# Thermal_CCM.net
KiCad netlist of a schematic drawn in Altium Designer
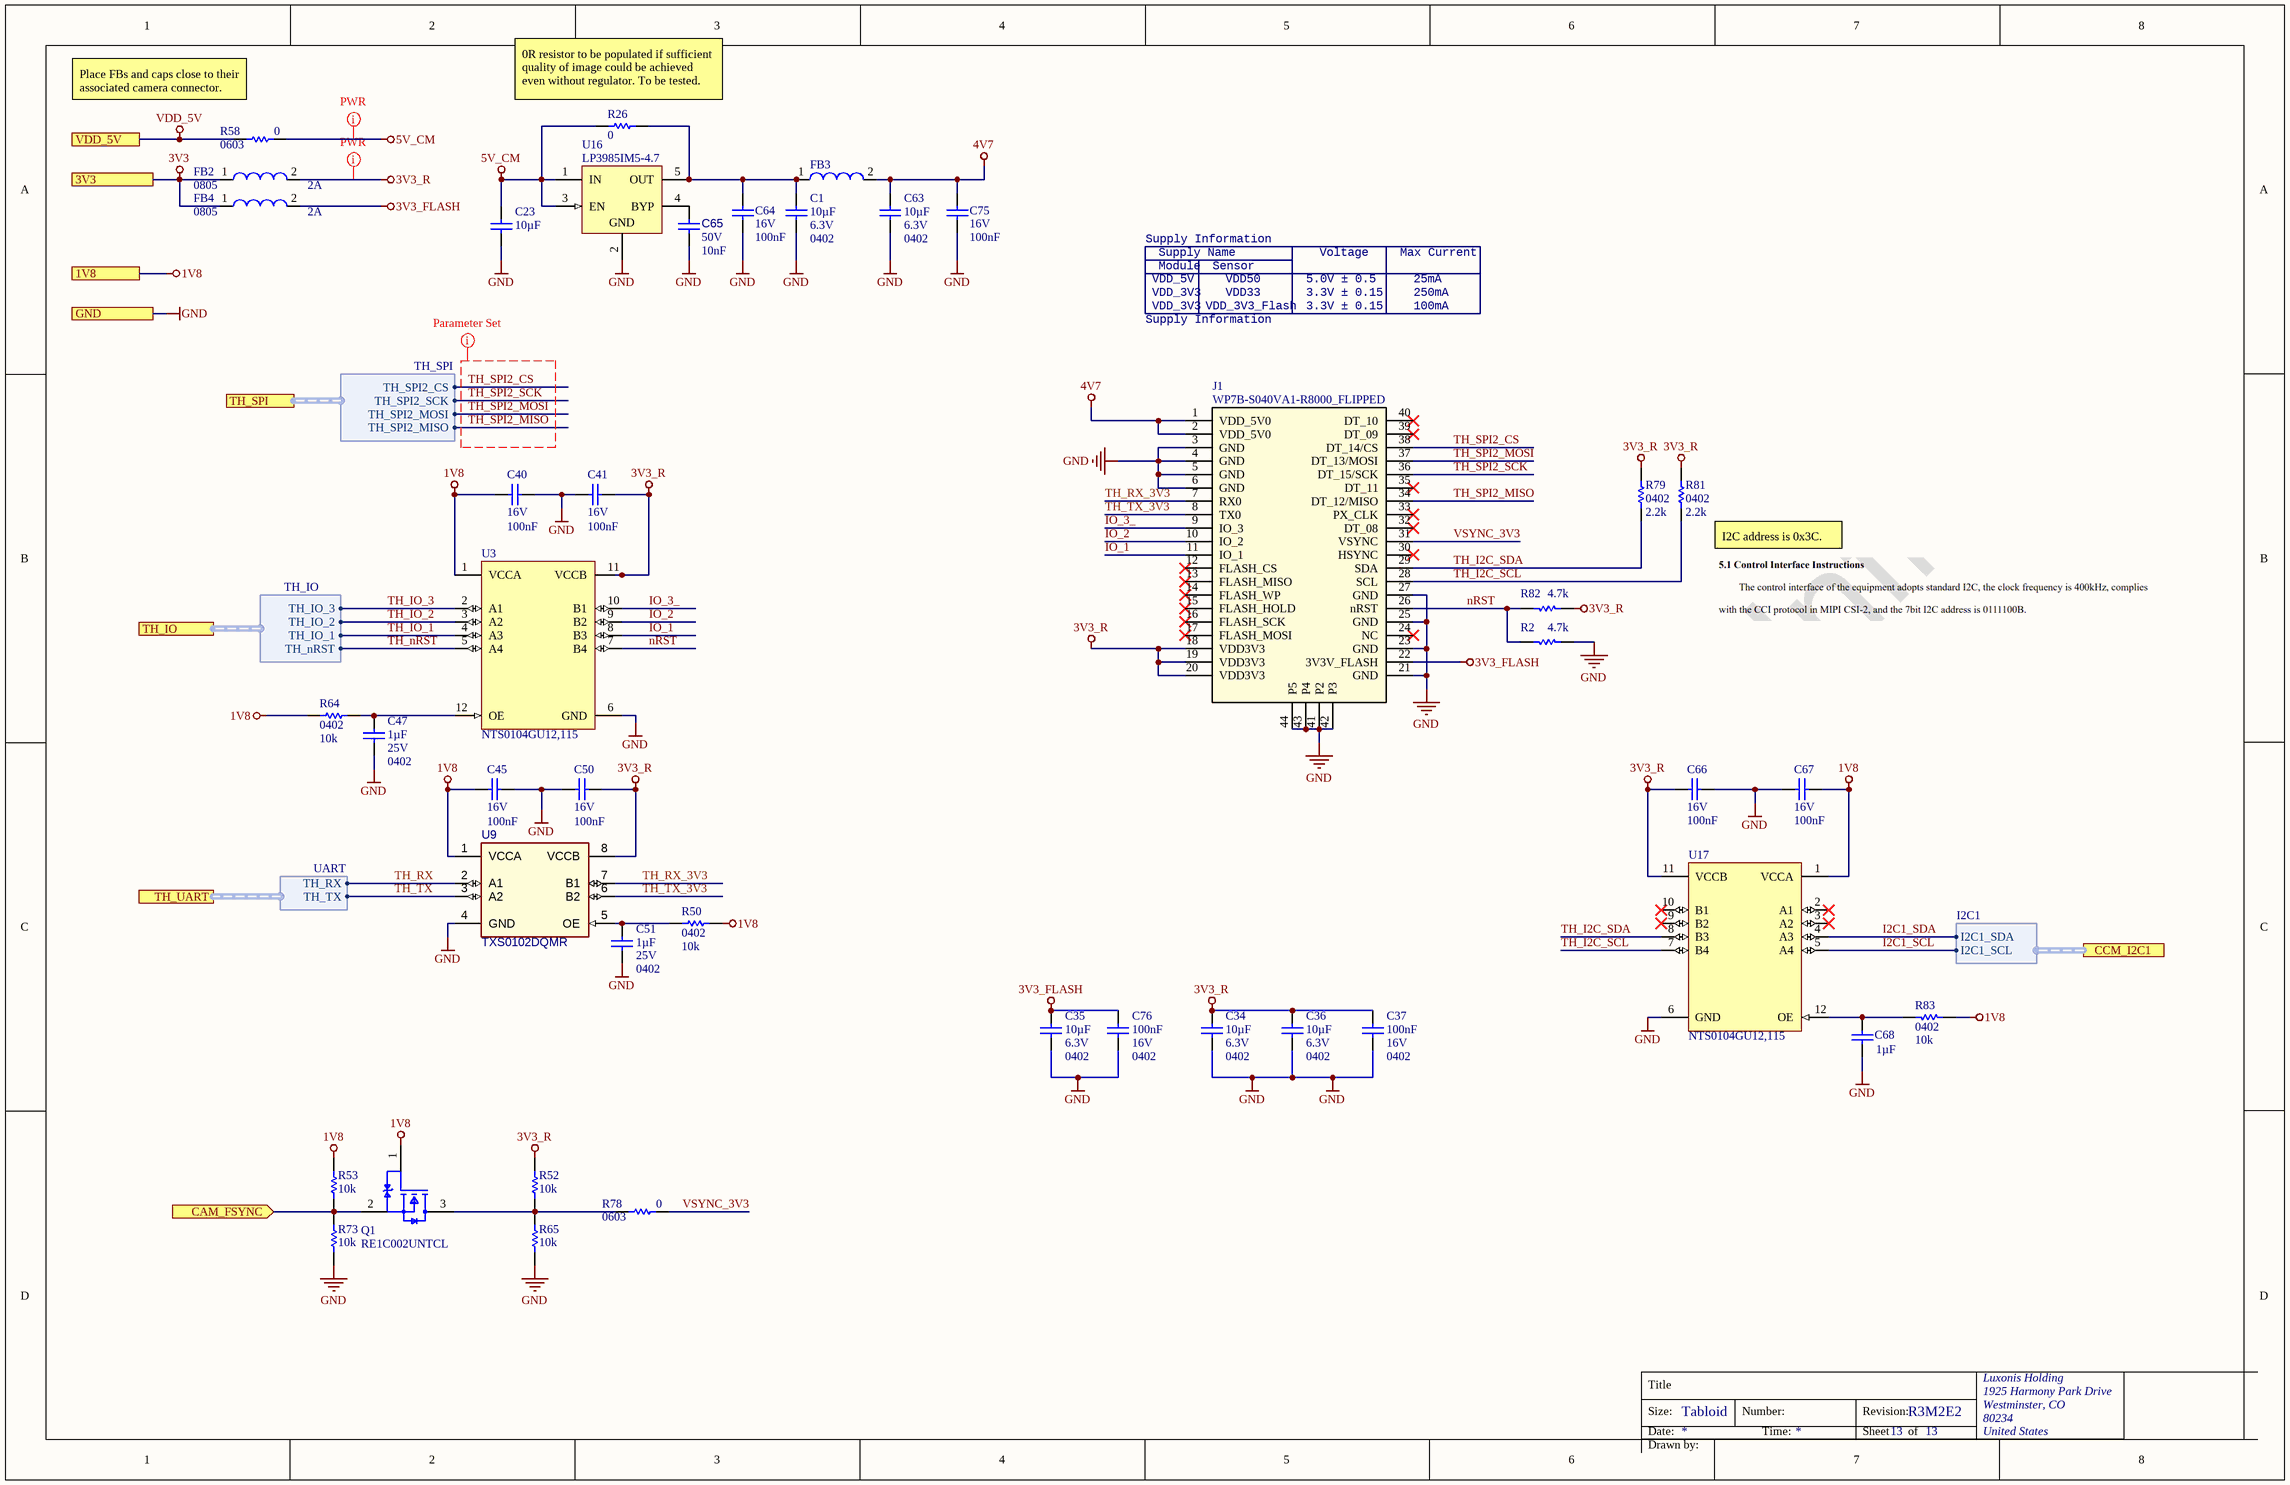
[diagram p0: Thermal_CCM.SchDoc]

(export (version "E")
  (design (tool "Eeschema 10.0.6"))
  (components
    (comp (ref "C1")
      (value "10µF")
      (footprint "CAPC0402(1005)70_N")
      (description "CAP CER 10UF 6.3V X5R 0402 20%")
      (fields
        (field (name "VOLTAGE RATING") "6.3V")
        (field (name "CASE/PACKAGE") "0402")
        (field (name "TOLERANCE") "20%")
        (field (name "Comment") "GRM155R60J106ME15D")
      )
      (libsource (lib "Luxonis LLC") (part "LLL153C70G474ME17E"))
    )
    (comp (ref "C23")
      (value "10µF")
      (footprint "CAPC0402(1005)70_L")
      (description "CAP CER 10UF 6.3V X5R 0402 20%")
      (fields (field (name "TOLERANCE") "20%") (field (name "Comment") "GRM155R60J106ME15D"))
      (libsource (lib "Luxonis LLC") (part "LLL153C70G474ME17E"))
    )
    (comp (ref "C34")
      (value "10µF")
      (footprint "CAPC0402(1005)70_L")
      (description "CAP CER 10UF 6.3V X5R 0402 20%")
      (fields
        (field (name "VOLTAGE RATING") "6.3V")
        (field (name "CASE/PACKAGE") "0402")
        (field (name "TOLERANCE") "20%")
        (field (name "Comment") "GRM155R60J106ME15D")
      )
      (libsource (lib "Luxonis LLC") (part "LLL153C70G474ME17E"))
    )
    (comp (ref "C35")
      (value "10µF")
      (footprint "CAPC0402(1005)70_L")
      (description "CAP CER 10UF 6.3V X5R 0402 20%")
      (fields
        (field (name "VOLTAGE RATING") "6.3V")
        (field (name "CASE/PACKAGE") "0402")
        (field (name "TOLERANCE") "20%")
        (field (name "Comment") "GRM155R60J106ME15D")
      )
      (libsource (lib "Luxonis LLC") (part "LLL153C70G474ME17E"))
    )
    (comp (ref "C36")
      (value "10µF")
      (footprint "CAPC0402(1005)70_L")
      (description "CAP CER 10UF 6.3V X5R 0402 20%")
      (fields
        (field (name "VOLTAGE RATING") "6.3V")
        (field (name "CASE/PACKAGE") "0402")
        (field (name "TOLERANCE") "20%")
        (field (name "Comment") "GRM155R60J106ME15D")
      )
      (libsource (lib "Luxonis LLC") (part "LLL153C70G474ME17E"))
    )
    (comp (ref "C37")
      (value "100nF")
      (footprint "CAPC0402(1005)60_L")
      (description "CAP CER 0.1UF 16V X7R 0402 10%")
      (fields
        (field (name "VOLTAGE RATING") "16V")
        (field (name "CASE/PACKAGE") "0402")
        (field (name "TOLERANCE") "10%")
        (field (name "Comment") "CL05B104KO5NFNC")
      )
      (libsource (lib "Luxonis LLC") (part "GRM188R61C475KAAJD"))
    )
    (comp (ref "C40")
      (value "100nF")
      (footprint "CAPC0402(1005)60_L")
      (description "CAP CER 0.1UF 16V X7R 0402 10%")
      (fields
        (field (name "VOLTAGE RATING") "16V")
        (field (name "TOLERANCE") "10%")
        (field (name "Comment") "CL05B104KO5NFNC")
      )
      (libsource (lib "Luxonis LLC") (part "GRM188R61C475KAAJD"))
    )
    (comp (ref "C41")
      (value "100nF")
      (footprint "CAPC0402(1005)60_L")
      (description "CAP CER 0.1UF 16V X7R 0402 10%")
      (fields
        (field (name "VOLTAGE RATING") "16V")
        (field (name "TOLERANCE") "10%")
        (field (name "Comment") "CL05B104KO5NFNC")
      )
      (libsource (lib "Luxonis LLC") (part "GRM188R61C475KAAJD"))
    )
    (comp (ref "C45")
      (value "100nF")
      (footprint "CAPC0402(1005)60_L")
      (description "CAP CER 0.1UF 16V X7R 0402 10%")
      (fields
        (field (name "VOLTAGE RATING") "16V")
        (field (name "TOLERANCE") "10%")
        (field (name "Comment") "CL05B104KO5NFNC")
      )
      (libsource (lib "Luxonis LLC") (part "GRM188R61C475KAAJD"))
    )
    (comp (ref "C47")
      (value "1µF")
      (footprint "CAPC0402(1005)70_L")
      (description "CAP CER 1UF 25V X5R 0402 10%")
      (fields
        (field (name "VOLTAGE RATING") "25V")
        (field (name "CASE/PACKAGE") "0402")
        (field (name "TOLERANCE") "10%")
        (field (name "Comment") "GRM155R61E105KA12D")
      )
      (libsource (lib "Luxonis LLC") (part "GRM188R61C475KAAJD"))
    )
    (comp (ref "C50")
      (value "100nF")
      (footprint "CAPC0402(1005)60_L")
      (description "CAP CER 0.1UF 16V X7R 0402 10%")
      (fields
        (field (name "VOLTAGE RATING") "16V")
        (field (name "TOLERANCE") "10%")
        (field (name "Comment") "CL05B104KO5NFNC")
      )
      (libsource (lib "Luxonis LLC") (part "GRM188R61C475KAAJD"))
    )
    (comp (ref "C51")
      (value "1µF")
      (footprint "CAPC0402(1005)70_L")
      (description "CAP CER 1UF 25V X5R 0402 10%")
      (fields
        (field (name "VOLTAGE RATING") "25V")
        (field (name "CASE/PACKAGE") "0402")
        (field (name "TOLERANCE") "10%")
        (field (name "Comment") "GRM155R61E105KA12D")
      )
      (libsource (lib "Luxonis LLC") (part "GRM188R61C475KAAJD"))
    )
    (comp (ref "C63")
      (value "10µF")
      (footprint "CAPC0402(1005)70_N")
      (description "CAP CER 10UF 6.3V X5R 0402 20%")
      (fields
        (field (name "VOLTAGE RATING") "6.3V")
        (field (name "CASE/PACKAGE") "0402")
        (field (name "TOLERANCE") "20%")
        (field (name "Comment") "GRM155R60J106ME15D")
      )
      (libsource (lib "Luxonis LLC") (part "LLL153C70G474ME17E"))
    )
    (comp (ref "C64")
      (value "100nF")
      (footprint "CAPC0402(1005)60_N")
      (description "CAP CER 0.1UF 16V X7R 0402 10%")
      (fields
        (field (name "VOLTAGE RATING") "16V")
        (field (name "TOLERANCE") "10%")
        (field (name "Comment") "CL05B104KO5NFNC")
      )
      (libsource (lib "Luxonis LLC") (part "GRM188R61C475KAAJD"))
    )
    (comp (ref "C65")
      (value "10nF")
      (footprint "CAPC0402(1005)60_L")
      (description "CAP CER 10nF 50V X7R 0402 5%")
      (fields
        (field (name "VOLTAGE RATING") "50V")
        (field (name "TOLERANCE") "5%")
        (field (name "Comment") "C0402C103K5RACTU")
      )
      (libsource (lib "Luxonis LLC") (part "*"))
    )
    (comp (ref "C66")
      (value "100nF")
      (footprint "CAPC0402(1005)60_L")
      (description "CAP CER 0.1UF 16V X7R 0402 10%")
      (fields
        (field (name "VOLTAGE RATING") "16V")
        (field (name "TOLERANCE") "10%")
        (field (name "Comment") "CL05B104KO5NFNC")
      )
      (libsource (lib "Luxonis LLC") (part "GRM188R61C475KAAJD"))
    )
    (comp (ref "C67")
      (value "100nF")
      (footprint "CAPC0402(1005)60_L")
      (description "CAP CER 0.1UF 16V X7R 0402 10%")
      (fields
        (field (name "VOLTAGE RATING") "16V")
        (field (name "TOLERANCE") "10%")
        (field (name "Comment") "CL05B104KO5NFNC")
      )
      (libsource (lib "Luxonis LLC") (part "GRM188R61C475KAAJD"))
    )
    (comp (ref "C68")
      (value "1µF")
      (footprint "CAPC0402(1005)70_L")
      (description "CAP CER 1UF 25V X5R 0402 10%")
      (fields (field (name "TOLERANCE") "10%") (field (name "Comment") "GRM155R61E105KA12D"))
      (libsource (lib "Luxonis LLC") (part "GRM188R61C475KAAJD"))
    )
    (comp (ref "C75")
      (value "100nF")
      (footprint "CAPC0402(1005)60_N")
      (description "CAP CER 0.1UF 16V X7R 0402 10%")
      (fields
        (field (name "VOLTAGE RATING") "16V")
        (field (name "TOLERANCE") "10%")
        (field (name "Comment") "CL05B104KO5NFNC")
      )
      (libsource (lib "Luxonis LLC") (part "GRM188R61C475KAAJD"))
    )
    (comp (ref "C76")
      (value "100nF")
      (footprint "CAPC0402(1005)60_L")
      (description "CAP CER 0.1UF 16V X7R 0402 10%")
      (fields
        (field (name "VOLTAGE RATING") "16V")
        (field (name "CASE/PACKAGE") "0402")
        (field (name "TOLERANCE") "10%")
        (field (name "Comment") "CL05B104KO5NFNC")
      )
      (libsource (lib "Luxonis LLC") (part "GRM188R61C475KAAJD"))
    )
    (comp (ref "FB2")
      (value "2508056017Y2")
      (footprint "2508056017Y2")
      (description "FERRITE BEAD, 0.1OHM, 2A, 0805, 600R/100MHz")
      (fields
        (field (name "CURRENT RATING") "2A")
        (field (name "CASE/PACKAGE") "0805")
        (field (name "TOLERANCE") "25%")
      )
      (libsource (lib "Luxonis LLC") (part "2508056017Y2"))
    )
    (comp (ref "FB3")
      (value "2508056017Y2")
      (footprint "2508056017Y2")
      (description "FERRITE BEAD, 0.1OHM, 2A, 0805, 600R/100MHz")
      (fields (field (name "TOLERANCE") "25%"))
      (libsource (lib "Luxonis LLC") (part "2508056017Y2"))
    )
    (comp (ref "FB4")
      (value "2508056017Y2")
      (footprint "2508056017Y2")
      (description "FERRITE BEAD, 0.1OHM, 2A, 0805, 600R/100MHz")
      (fields
        (field (name "CURRENT RATING") "2A")
        (field (name "CASE/PACKAGE") "0805")
        (field (name "TOLERANCE") "25%")
      )
      (libsource (lib "Luxonis LLC") (part "2508056017Y2"))
    )
    (comp (ref "J1")
      (value "WP7B-S040VA1-R8000_FLIPPED")
      (footprint "WP7B-S040VA1-R8000-Edge mount")
      (libsource (lib "Luxonis LLC") (part "WP7B-P040VA1-R8000"))
    )
    (comp (ref "Q1")
      (value "RE1C002UNTCL")
      (footprint "RE1C002UNTCL")
      (description "MOSFET N-CH 20V 0.2A EMT3")
      (libsource (lib "Luxonis LLC") (part "RE1C002UNTCL"))
    )
    (comp (ref "R2")
      (value "4.7k")
      (footprint "RESC0402(1005)_L")
      (description "RES SMD 4.7K OHM 1% 1/16W 0402")
      (fields (field (name "TOLERANCE") "1%") (field (name "Comment") "RC0402FR-074K7L"))
      (libsource (lib "Luxonis LLC") (part "Default resistor symbol"))
    )
    (comp (ref "R26")
      (value "0")
      (footprint "RESC0603(1608)_N")
      (description "RES SMD 0 OHM 5% 1/10W 0603")
      (fields (field (name "TOLERANCE") "5%") (field (name "Comment") "CRCW06030000Z0EA"))
      (libsource (lib "Luxonis LLC") (part "RC0402FR-0722RL_1"))
    )
    (comp (ref "R50")
      (value "10k")
      (footprint "RESC0402(1005)_L")
      (description "RES SMD 10K OHM 1% 1/16W 0402")
      (fields
        (field (name "CASE/PACKAGE") "0402")
        (field (name "TOLERANCE") "1%")
        (field (name "Comment") "RC0402FR-1310KL")
      )
      (libsource (lib "Luxonis LLC") (part "RC0402FR-0722RL_1"))
    )
    (comp (ref "R52")
      (value "10k")
      (footprint "RESC0402(1005)_L")
      (description "RES SMD 10K OHM 1% 1/16W 0402")
      (fields (field (name "TOLERANCE") "1%") (field (name "Comment") "RC0402FR-1310KL"))
      (libsource (lib "Luxonis LLC") (part "RC0402FR-0722RL_1"))
    )
    (comp (ref "R53")
      (value "10k")
      (footprint "RESC0402(1005)_L")
      (description "RES SMD 10K OHM 1% 1/16W 0402")
      (fields (field (name "TOLERANCE") "1%") (field (name "Comment") "RC0402FR-1310KL"))
      (libsource (lib "Luxonis LLC") (part "RC0402FR-0722RL_1"))
    )
    (comp (ref "R58")
      (value "0")
      (footprint "RESC0603(1608)_N")
      (description "RES SMD 0 OHM 5% 1/10W 0603")
      (fields
        (field (name "TOLERANCE") "5%")
        (field (name "CASE/PACKAGE") "0603")
        (field (name "Comment") "CRCW06030000Z0EA")
      )
      (libsource (lib "Luxonis LLC") (part "RC0402FR-0722RL_1"))
    )
    (comp (ref "R64")
      (value "10k")
      (footprint "RESC0402(1005)_L")
      (description "RES SMD 10K OHM 1% 1/16W 0402")
      (fields
        (field (name "CASE/PACKAGE") "0402")
        (field (name "TOLERANCE") "1%")
        (field (name "Comment") "RC0402FR-1310KL")
      )
      (libsource (lib "Luxonis LLC") (part "RC0402FR-0722RL_1"))
    )
    (comp (ref "R65")
      (value "10k")
      (footprint "RESC0402(1005)_L")
      (description "RES SMD 10K OHM 1% 1/16W 0402")
      (fields (field (name "TOLERANCE") "1%") (field (name "Comment") "RC0402FR-1310KL"))
      (libsource (lib "Luxonis LLC") (part "RC0402FR-0722RL_1"))
    )
    (comp (ref "R73")
      (value "10k")
      (footprint "RESC0402(1005)_L")
      (description "RES SMD 10K OHM 1% 1/16W 0402")
      (fields (field (name "TOLERANCE") "1%") (field (name "Comment") "RC0402FR-1310KL"))
      (libsource (lib "Luxonis LLC") (part "RC0402FR-0722RL_1"))
    )
    (comp (ref "R78")
      (value "0")
      (footprint "RESC0603(1608)_N")
      (description "RES SMD 0 OHM 5% 1/10W 0603")
      (fields
        (field (name "TOLERANCE") "5%")
        (field (name "CASE/PACKAGE") "0603")
        (field (name "Comment") "CRCW06030000Z0EA")
      )
      (libsource (lib "Luxonis LLC") (part "RC0402FR-0722RL_1"))
    )
    (comp (ref "R79")
      (value "2.2k")
      (footprint "RESC0402(1005)_L")
      (description "RES SMD 2.2K OHM 1% 1/16W 0402")
      (fields
        (field (name "CASE/PACKAGE") "0402")
        (field (name "TOLERANCE") "1%")
        (field (name "Comment") "RC0402FR-072K2L")
      )
      (libsource (lib "Luxonis LLC") (part "Default resistor symbol"))
    )
    (comp (ref "R81")
      (value "2.2k")
      (footprint "RESC0402(1005)_L")
      (description "RES SMD 2.2K OHM 1% 1/16W 0402")
      (fields
        (field (name "CASE/PACKAGE") "0402")
        (field (name "TOLERANCE") "1%")
        (field (name "Comment") "RC0402FR-072K2L")
      )
      (libsource (lib "Luxonis LLC") (part "Default resistor symbol"))
    )
    (comp (ref "R82")
      (value "4.7k")
      (footprint "RESC0402(1005)_L")
      (description "RES SMD 4.7K OHM 1% 1/16W 0402")
      (fields (field (name "TOLERANCE") "1%") (field (name "Comment") "RC0402FR-074K7L"))
      (libsource (lib "Luxonis LLC") (part "Default resistor symbol"))
    )
    (comp (ref "R83")
      (value "10k")
      (footprint "RESC0402(1005)_L")
      (description "RES SMD 10K OHM 1% 1/16W 0402")
      (fields
        (field (name "CASE/PACKAGE") "0402")
        (field (name "TOLERANCE") "1%")
        (field (name "Comment") "RC0402FR-1310KL")
      )
      (libsource (lib "Luxonis LLC") (part "RC0402FR-0722RL_1"))
    )
    (comp (ref "U3")
      (value "NTS0104GU12,115")
      (footprint "QFN40P170X200X50-12N")
      (description "Voltage Level Translator Bidirectional 1 Circuit 4 Channel 50Mbps 12-XQFN _2x1.7_")
      (libsource (lib "") (part "NTS0104GU12,115_1"))
    )
    (comp (ref "U9")
      (value "TXS0102DQMR")
      (footprint "DQM")
      (description "IC TRANSLATOR VOLTAGE 8-X2SON")
      (libsource (lib "Luxonis LLC") (part "CMP-001-0022-1"))
    )
    (comp (ref "U16")
      (value "LP3985IM5-4.7")
      (footprint "DBV0005A_L")
      (description "LDO Regulator Pos 4.7V 0.15A 5-Pin SOT-23 T/R")
      (libsource (lib "Luxonis LLC") (part "PM-REG-LP3985-SOT5"))
    )
    (comp (ref "U17")
      (value "NTS0104GU12,115")
      (footprint "QFN40P170X200X50-12N")
      (description "Voltage Level Translator Bidirectional 1 Circuit 4 Channel 50Mbps 12-XQFN _2x1.7_")
      (libsource (lib "Luxonis LLC") (part "NTS0104GU12,115"))
    )
  )
  (nets
    (net (code "5") (name "/CAM_FSYNC") (class "Default")
      (node (ref "Q1") (pin "2") (pinfunction "Source_2") (pintype "passive"))
      (node (ref "R53") (pin "1") (pinfunction "1_1") (pintype "passive"))
      (node (ref "R73") (pin "2") (pinfunction "2_2") (pintype "passive"))
    )
    (net (code "6") (name "/I2C1_SCL") (class "Default")
      (node (ref "U17") (pin "5") (pinfunction "A4_5") (pintype "bidirectional"))
    )
    (net (code "7") (name "/I2C1_SDA") (class "Default")
      (node (ref "U17") (pin "4") (pinfunction "A3_4") (pintype "bidirectional"))
    )
    (net (code "8") (name "/IO_1") (class "Default")
      (node (ref "J1") (pin "11") (pinfunction "IO_1_11") (pintype "passive"))
      (node (ref "U3") (pin "8") (pinfunction "B3_8") (pintype "bidirectional"))
    )
    (net (code "9") (name "/IO_2") (class "Default")
      (node (ref "J1") (pin "10") (pinfunction "IO_2_10") (pintype "passive"))
      (node (ref "U3") (pin "9") (pinfunction "B2_9") (pintype "bidirectional"))
    )
    (net (code "10") (name "/IO_3_") (class "Default")
      (node (ref "J1") (pin "9") (pinfunction "IO_3_9") (pintype "passive"))
      (node (ref "U3") (pin "10") (pinfunction "B1_10") (pintype "bidirectional"))
    )
    (net (code "11") (name "/TH_I2C_SCL") (class "Default")
      (node (ref "J1") (pin "28") (pinfunction "SCL_28") (pintype "passive"))
      (node (ref "R81") (pin "1") (pinfunction "1_1") (pintype "passive"))
      (node (ref "U17") (pin "7") (pinfunction "B4_7") (pintype "bidirectional"))
    )
    (net (code "12") (name "/TH_I2C_SDA") (class "Default")
      (node (ref "J1") (pin "29") (pinfunction "SDA_29") (pintype "passive"))
      (node (ref "R79") (pin "1") (pinfunction "1_1") (pintype "passive"))
      (node (ref "U17") (pin "8") (pinfunction "B3_8") (pintype "bidirectional"))
    )
    (net (code "13") (name "/TH_IO_1") (class "Default")
      (node (ref "U3") (pin "4") (pinfunction "A3_4") (pintype "bidirectional"))
    )
    (net (code "14") (name "/TH_IO_2") (class "Default")
      (node (ref "U3") (pin "3") (pinfunction "A2_3") (pintype "bidirectional"))
    )
    (net (code "15") (name "/TH_IO_3") (class "Default")
      (node (ref "U3") (pin "2") (pinfunction "A1_2") (pintype "bidirectional"))
    )
    (net (code "16") (name "/TH_RX") (class "Default")
      (node (ref "U9") (pin "2") (pinfunction "A1_2") (pintype "bidirectional"))
    )
    (net (code "17") (name "/TH_RX_3V3") (class "Default")
      (node (ref "J1") (pin "7") (pinfunction "RX0_7") (pintype "passive"))
      (node (ref "U9") (pin "7") (pinfunction "B1_7") (pintype "bidirectional"))
    )
    (net (code "18") (name "/TH_SPI2_CS") (class "Default")
      (node (ref "J1") (pin "38") (pinfunction "DT_14/CS_38") (pintype "passive"))
    )
    (net (code "19") (name "/TH_SPI2_MISO") (class "Default")
      (node (ref "J1") (pin "34") (pinfunction "DT_12/MISO_34") (pintype "passive"))
    )
    (net (code "20") (name "/TH_SPI2_MOSI") (class "Default")
      (node (ref "J1") (pin "37") (pinfunction "DT_13/MOSI_37") (pintype "passive"))
    )
    (net (code "21") (name "/TH_SPI2_SCK") (class "Default")
      (node (ref "J1") (pin "36") (pinfunction "DT_15/SCK_36") (pintype "passive"))
    )
    (net (code "22") (name "/TH_TX") (class "Default")
      (node (ref "U9") (pin "3") (pinfunction "A2_3") (pintype "bidirectional"))
    )
    (net (code "23") (name "/TH_TX_3V3") (class "Default")
      (node (ref "J1") (pin "8") (pinfunction "TX0_8") (pintype "passive"))
      (node (ref "U9") (pin "6") (pinfunction "B2_6") (pintype "bidirectional"))
    )
    (net (code "24") (name "/TH_nRST") (class "Default")
      (node (ref "U3") (pin "5") (pinfunction "A4_5") (pintype "bidirectional"))
    )
    (net (code "25") (name "/VSYNC_3V3") (class "Default")
      (node (ref "J1") (pin "31") (pinfunction "VSYNC_31") (pintype "passive"))
      (node (ref "R78") (pin "2") (pinfunction "2_2") (pintype "passive"))
    )
    (net (code "26") (name "/nRST") (class "Default")
      (node (ref "J1") (pin "26") (pinfunction "nRST_26") (pintype "passive"))
      (node (ref "R2") (pin "1") (pinfunction "1_1") (pintype "passive"))
      (node (ref "R82") (pin "1") (pinfunction "1_1") (pintype "passive"))
      (node (ref "U3") (pin "7") (pinfunction "B4_7") (pintype "bidirectional"))
    )
    (net (code "31") (name "1V8") (class "Default")
      (node (ref "C40") (pin "2") (pinfunction "2_2") (pintype "passive"))
      (node (ref "C45") (pin "2") (pinfunction "2_2") (pintype "passive"))
      (node (ref "C67") (pin "2") (pinfunction "2_2") (pintype "passive"))
      (node (ref "Q1") (pin "1") (pinfunction "Gate_1") (pintype "passive"))
      (node (ref "R50") (pin "2") (pinfunction "2_2") (pintype "passive"))
      (node (ref "R53") (pin "2") (pinfunction "2_2") (pintype "passive"))
      (node (ref "R64") (pin "2") (pinfunction "2_2") (pintype "passive"))
      (node (ref "R83") (pin "2") (pinfunction "2_2") (pintype "passive"))
      (node (ref "U17") (pin "1") (pinfunction "VCCA_1") (pintype "power_in"))
      (node (ref "U3") (pin "1") (pinfunction "VCCA_1") (pintype "power_in"))
      (node (ref "U9") (pin "1") (pinfunction "VCCA_1") (pintype "power_in"))
    )
    (net (code "32") (name "3V3") (class "Default")
      (node (ref "FB2") (pin "1") (pinfunction "1_1") (pintype "passive"))
      (node (ref "FB4") (pin "1") (pinfunction "1_1") (pintype "passive"))
    )
    (net (code "33") (name "3V3_FLASH") (class "Default")
      (node (ref "C35") (pin "2") (pinfunction "2_2") (pintype "passive"))
      (node (ref "C76") (pin "2") (pinfunction "2_2") (pintype "passive"))
      (node (ref "FB4") (pin "2") (pinfunction "2_2") (pintype "passive"))
      (node (ref "J1") (pin "22") (pinfunction "3V3V_FLASH_22") (pintype "passive"))
    )
    (net (code "34") (name "3V3_R") (class "Default")
      (node (ref "C34") (pin "2") (pinfunction "2_2") (pintype "passive"))
      (node (ref "C36") (pin "2") (pinfunction "2_2") (pintype "passive"))
      (node (ref "C37") (pin "2") (pinfunction "2_2") (pintype "passive"))
      (node (ref "C41") (pin "1") (pinfunction "1_1") (pintype "passive"))
      (node (ref "C50") (pin "1") (pinfunction "1_1") (pintype "passive"))
      (node (ref "C66") (pin "1") (pinfunction "1_1") (pintype "passive"))
      (node (ref "FB2") (pin "2") (pinfunction "2_2") (pintype "passive"))
      (node (ref "J1") (pin "18") (pinfunction "VDD3V3_18") (pintype "passive"))
      (node (ref "J1") (pin "19") (pinfunction "VDD3V3_19") (pintype "passive"))
      (node (ref "J1") (pin "20") (pinfunction "VDD3V3_20") (pintype "passive"))
      (node (ref "R52") (pin "2") (pinfunction "2_2") (pintype "passive"))
      (node (ref "R79") (pin "2") (pinfunction "2_2") (pintype "passive"))
      (node (ref "R81") (pin "2") (pinfunction "2_2") (pintype "passive"))
      (node (ref "R82") (pin "2") (pinfunction "2_2") (pintype "passive"))
      (node (ref "U17") (pin "11") (pinfunction "VCCB_11") (pintype "power_in"))
      (node (ref "U3") (pin "11") (pinfunction "VCCB_11") (pintype "power_in"))
      (node (ref "U9") (pin "8") (pinfunction "VCCB_8") (pintype "power_in"))
    )
    (net (code "35") (name "4V7") (class "Default")
      (node (ref "C63") (pin "2") (pinfunction "2_2") (pintype "passive"))
      (node (ref "C75") (pin "1") (pinfunction "1_1") (pintype "passive"))
      (node (ref "FB3") (pin "2") (pinfunction "2_2") (pintype "passive"))
      (node (ref "J1") (pin "1") (pinfunction "VDD_5V0_1") (pintype "passive"))
      (node (ref "J1") (pin "2") (pinfunction "VDD_5V0_2") (pintype "passive"))
    )
    (net (code "36") (name "5V_CM") (class "Default")
      (node (ref "C23") (pin "2") (pinfunction "2_2") (pintype "passive"))
      (node (ref "R26") (pin "1") (pinfunction "1_1") (pintype "passive"))
      (node (ref "R58") (pin "2") (pinfunction "2_2") (pintype "passive"))
      (node (ref "U16") (pin "1") (pinfunction "IN_1") (pintype "power_in"))
      (node (ref "U16") (pin "3") (pinfunction "EN_3") (pintype "input"))
    )
    (net (code "37") (name "GND") (class "Default")
      (node (ref "C1") (pin "1") (pinfunction "1_1") (pintype "passive"))
      (node (ref "C23") (pin "1") (pinfunction "1_1") (pintype "passive"))
      (node (ref "C34") (pin "1") (pinfunction "1_1") (pintype "passive"))
      (node (ref "C35") (pin "1") (pinfunction "1_1") (pintype "passive"))
      (node (ref "C36") (pin "1") (pinfunction "1_1") (pintype "passive"))
      (node (ref "C37") (pin "1") (pinfunction "1_1") (pintype "passive"))
      (node (ref "C40") (pin "1") (pinfunction "1_1") (pintype "passive"))
      (node (ref "C41") (pin "2") (pinfunction "2_2") (pintype "passive"))
      (node (ref "C45") (pin "1") (pinfunction "1_1") (pintype "passive"))
      (node (ref "C47") (pin "1") (pinfunction "1_1") (pintype "passive"))
      (node (ref "C50") (pin "2") (pinfunction "2_2") (pintype "passive"))
      (node (ref "C51") (pin "1") (pinfunction "1_1") (pintype "passive"))
      (node (ref "C63") (pin "1") (pinfunction "1_1") (pintype "passive"))
      (node (ref "C64") (pin "2") (pinfunction "2_2") (pintype "passive"))
      (node (ref "C65") (pin "1") (pinfunction "1_1") (pintype "passive"))
      (node (ref "C66") (pin "2") (pinfunction "2_2") (pintype "passive"))
      (node (ref "C67") (pin "1") (pinfunction "1_1") (pintype "passive"))
      (node (ref "C68") (pin "1") (pinfunction "1_1") (pintype "passive"))
      (node (ref "C75") (pin "2") (pinfunction "2_2") (pintype "passive"))
      (node (ref "C76") (pin "1") (pinfunction "1_1") (pintype "passive"))
      (node (ref "J1") (pin "21") (pinfunction "GND_21") (pintype "passive"))
      (node (ref "J1") (pin "23") (pinfunction "GND_23") (pintype "passive"))
      (node (ref "J1") (pin "25") (pinfunction "GND_25") (pintype "passive"))
      (node (ref "J1") (pin "27") (pinfunction "GND_27") (pintype "passive"))
      (node (ref "J1") (pin "3") (pinfunction "GND_3") (pintype "passive"))
      (node (ref "J1") (pin "4") (pinfunction "GND_4") (pintype "passive"))
      (node (ref "J1") (pin "41") (pinfunction "P2_41") (pintype "passive"))
      (node (ref "J1") (pin "42") (pinfunction "P3_42") (pintype "passive"))
      (node (ref "J1") (pin "43") (pinfunction "P4_43") (pintype "passive"))
      (node (ref "J1") (pin "44") (pinfunction "P5_44") (pintype "passive"))
      (node (ref "J1") (pin "5") (pinfunction "GND_5") (pintype "passive"))
      (node (ref "J1") (pin "6") (pinfunction "GND_6") (pintype "passive"))
      (node (ref "R2") (pin "2") (pinfunction "2_2") (pintype "passive"))
      (node (ref "R65") (pin "1") (pinfunction "1_1") (pintype "passive"))
      (node (ref "R73") (pin "1") (pinfunction "1_1") (pintype "passive"))
      (node (ref "U16") (pin "2") (pinfunction "GND_2") (pintype "power_in"))
      (node (ref "U17") (pin "6") (pinfunction "GND_6") (pintype "power_in"))
      (node (ref "U3") (pin "6") (pinfunction "GND_6") (pintype "power_in"))
      (node (ref "U9") (pin "4") (pinfunction "GND_4") (pintype "power_in"))
    )
    (net (code "38") (name "Net-(Q1-Drain)") (class "Default")
      (node (ref "Q1") (pin "3") (pinfunction "Drain_3") (pintype "passive"))
      (node (ref "R52") (pin "1") (pinfunction "1_1") (pintype "passive"))
      (node (ref "R65") (pin "2") (pinfunction "2_2") (pintype "passive"))
      (node (ref "R78") (pin "1") (pinfunction "1_1") (pintype "passive"))
    )
    (net (code "39") (name "Net-(U3-OE)") (class "Default")
      (node (ref "C47") (pin "2") (pinfunction "2_2") (pintype "passive"))
      (node (ref "R64") (pin "1") (pinfunction "1_1") (pintype "passive"))
      (node (ref "U3") (pin "12") (pinfunction "OE_12") (pintype "input"))
    )
    (net (code "40") (name "Net-(U9-OE)") (class "Default")
      (node (ref "C51") (pin "2") (pinfunction "2_2") (pintype "passive"))
      (node (ref "R50") (pin "1") (pinfunction "1_1") (pintype "passive"))
      (node (ref "U9") (pin "5") (pinfunction "OE_5") (pintype "input"))
    )
    (net (code "41") (name "Net-(U16-BYP)") (class "Default")
      (node (ref "C65") (pin "2") (pinfunction "2_2") (pintype "passive"))
      (node (ref "U16") (pin "4") (pinfunction "BYP_4") (pintype "passive"))
    )
    (net (code "42") (name "Net-(U16-OUT)") (class "Default")
      (node (ref "C1") (pin "2") (pinfunction "2_2") (pintype "passive"))
      (node (ref "C64") (pin "1") (pinfunction "1_1") (pintype "passive"))
      (node (ref "FB3") (pin "1") (pinfunction "1_1") (pintype "passive"))
      (node (ref "R26") (pin "2") (pinfunction "2_2") (pintype "passive"))
      (node (ref "U16") (pin "5") (pinfunction "OUT_5") (pintype "power_in"))
    )
    (net (code "43") (name "Net-(U17-OE)") (class "Default")
      (node (ref "C68") (pin "2") (pinfunction "2_2") (pintype "passive"))
      (node (ref "R83") (pin "1") (pinfunction "1_1") (pintype "passive"))
      (node (ref "U17") (pin "12") (pinfunction "OE_12") (pintype "input"))
    )
    (net (code "44") (name "VDD_5V") (class "Default")
      (node (ref "R58") (pin "1") (pinfunction "1_1") (pintype "passive"))
    )
    (net (code "45") (name "unconnected-(J1-DT_08-Pad32)") (class "Default")
      (node (ref "J1") (pin "32") (pinfunction "DT_08_32") (pintype "passive+no_connect"))
    )
    (net (code "46") (name "unconnected-(J1-DT_09-Pad39)") (class "Default")
      (node (ref "J1") (pin "39") (pinfunction "DT_09_39") (pintype "passive+no_connect"))
    )
    (net (code "47") (name "unconnected-(J1-DT_10-Pad40)") (class "Default")
      (node (ref "J1") (pin "40") (pinfunction "DT_10_40") (pintype "passive+no_connect"))
    )
    (net (code "48") (name "unconnected-(J1-DT_11-Pad35)") (class "Default")
      (node (ref "J1") (pin "35") (pinfunction "DT_11_35") (pintype "passive+no_connect"))
    )
    (net (code "49") (name "unconnected-(J1-FLASH_CS-Pad12)") (class "Default")
      (node (ref "J1") (pin "12") (pinfunction "FLASH_CS_12") (pintype "passive+no_connect"))
    )
    (net (code "50") (name "unconnected-(J1-FLASH_HOLD-Pad15)") (class "Default")
      (node (ref "J1") (pin "15") (pinfunction "FLASH_HOLD_15") (pintype "passive+no_connect"))
    )
    (net (code "51") (name "unconnected-(J1-FLASH_MISO-Pad13)") (class "Default")
      (node (ref "J1") (pin "13") (pinfunction "FLASH_MISO_13") (pintype "passive+no_connect"))
    )
    (net (code "52") (name "unconnected-(J1-FLASH_MOSI-Pad17)") (class "Default")
      (node (ref "J1") (pin "17") (pinfunction "FLASH_MOSI_17") (pintype "passive+no_connect"))
    )
    (net (code "53") (name "unconnected-(J1-FLASH_SCK-Pad16)") (class "Default")
      (node (ref "J1") (pin "16") (pinfunction "FLASH_SCK_16") (pintype "passive+no_connect"))
    )
    (net (code "54") (name "unconnected-(J1-FLASH_WP-Pad14)") (class "Default")
      (node (ref "J1") (pin "14") (pinfunction "FLASH_WP_14") (pintype "passive+no_connect"))
    )
    (net (code "55") (name "unconnected-(J1-HSYNC-Pad30)") (class "Default")
      (node (ref "J1") (pin "30") (pinfunction "HSYNC_30") (pintype "passive+no_connect"))
    )
    (net (code "56") (name "unconnected-(J1-NC-Pad24)") (class "Default")
      (node (ref "J1") (pin "24") (pinfunction "NC_24") (pintype "passive+no_connect"))
    )
    (net (code "57") (name "unconnected-(J1-PX_CLK-Pad33)") (class "Default")
      (node (ref "J1") (pin "33") (pinfunction "PX_CLK_33") (pintype "passive+no_connect"))
    )
    (net (code "58") (name "unconnected-(U17-A1-Pad2)") (class "Default")
      (node (ref "U17") (pin "2") (pinfunction "A1_2") (pintype "bidirectional+no_connect"))
    )
    (net (code "59") (name "unconnected-(U17-A2-Pad3)") (class "Default")
      (node (ref "U17") (pin "3") (pinfunction "A2_3") (pintype "bidirectional+no_connect"))
    )
    (net (code "60") (name "unconnected-(U17-B1-Pad10)") (class "Default")
      (node (ref "U17") (pin "10") (pinfunction "B1_10") (pintype "bidirectional+no_connect"))
    )
    (net (code "61") (name "unconnected-(U17-B2-Pad9)") (class "Default")
      (node (ref "U17") (pin "9") (pinfunction "B2_9") (pintype "bidirectional+no_connect"))
    )
  )
)
